# 03-2G.net
KiCad netlist of a schematic drawn in Altium Designer
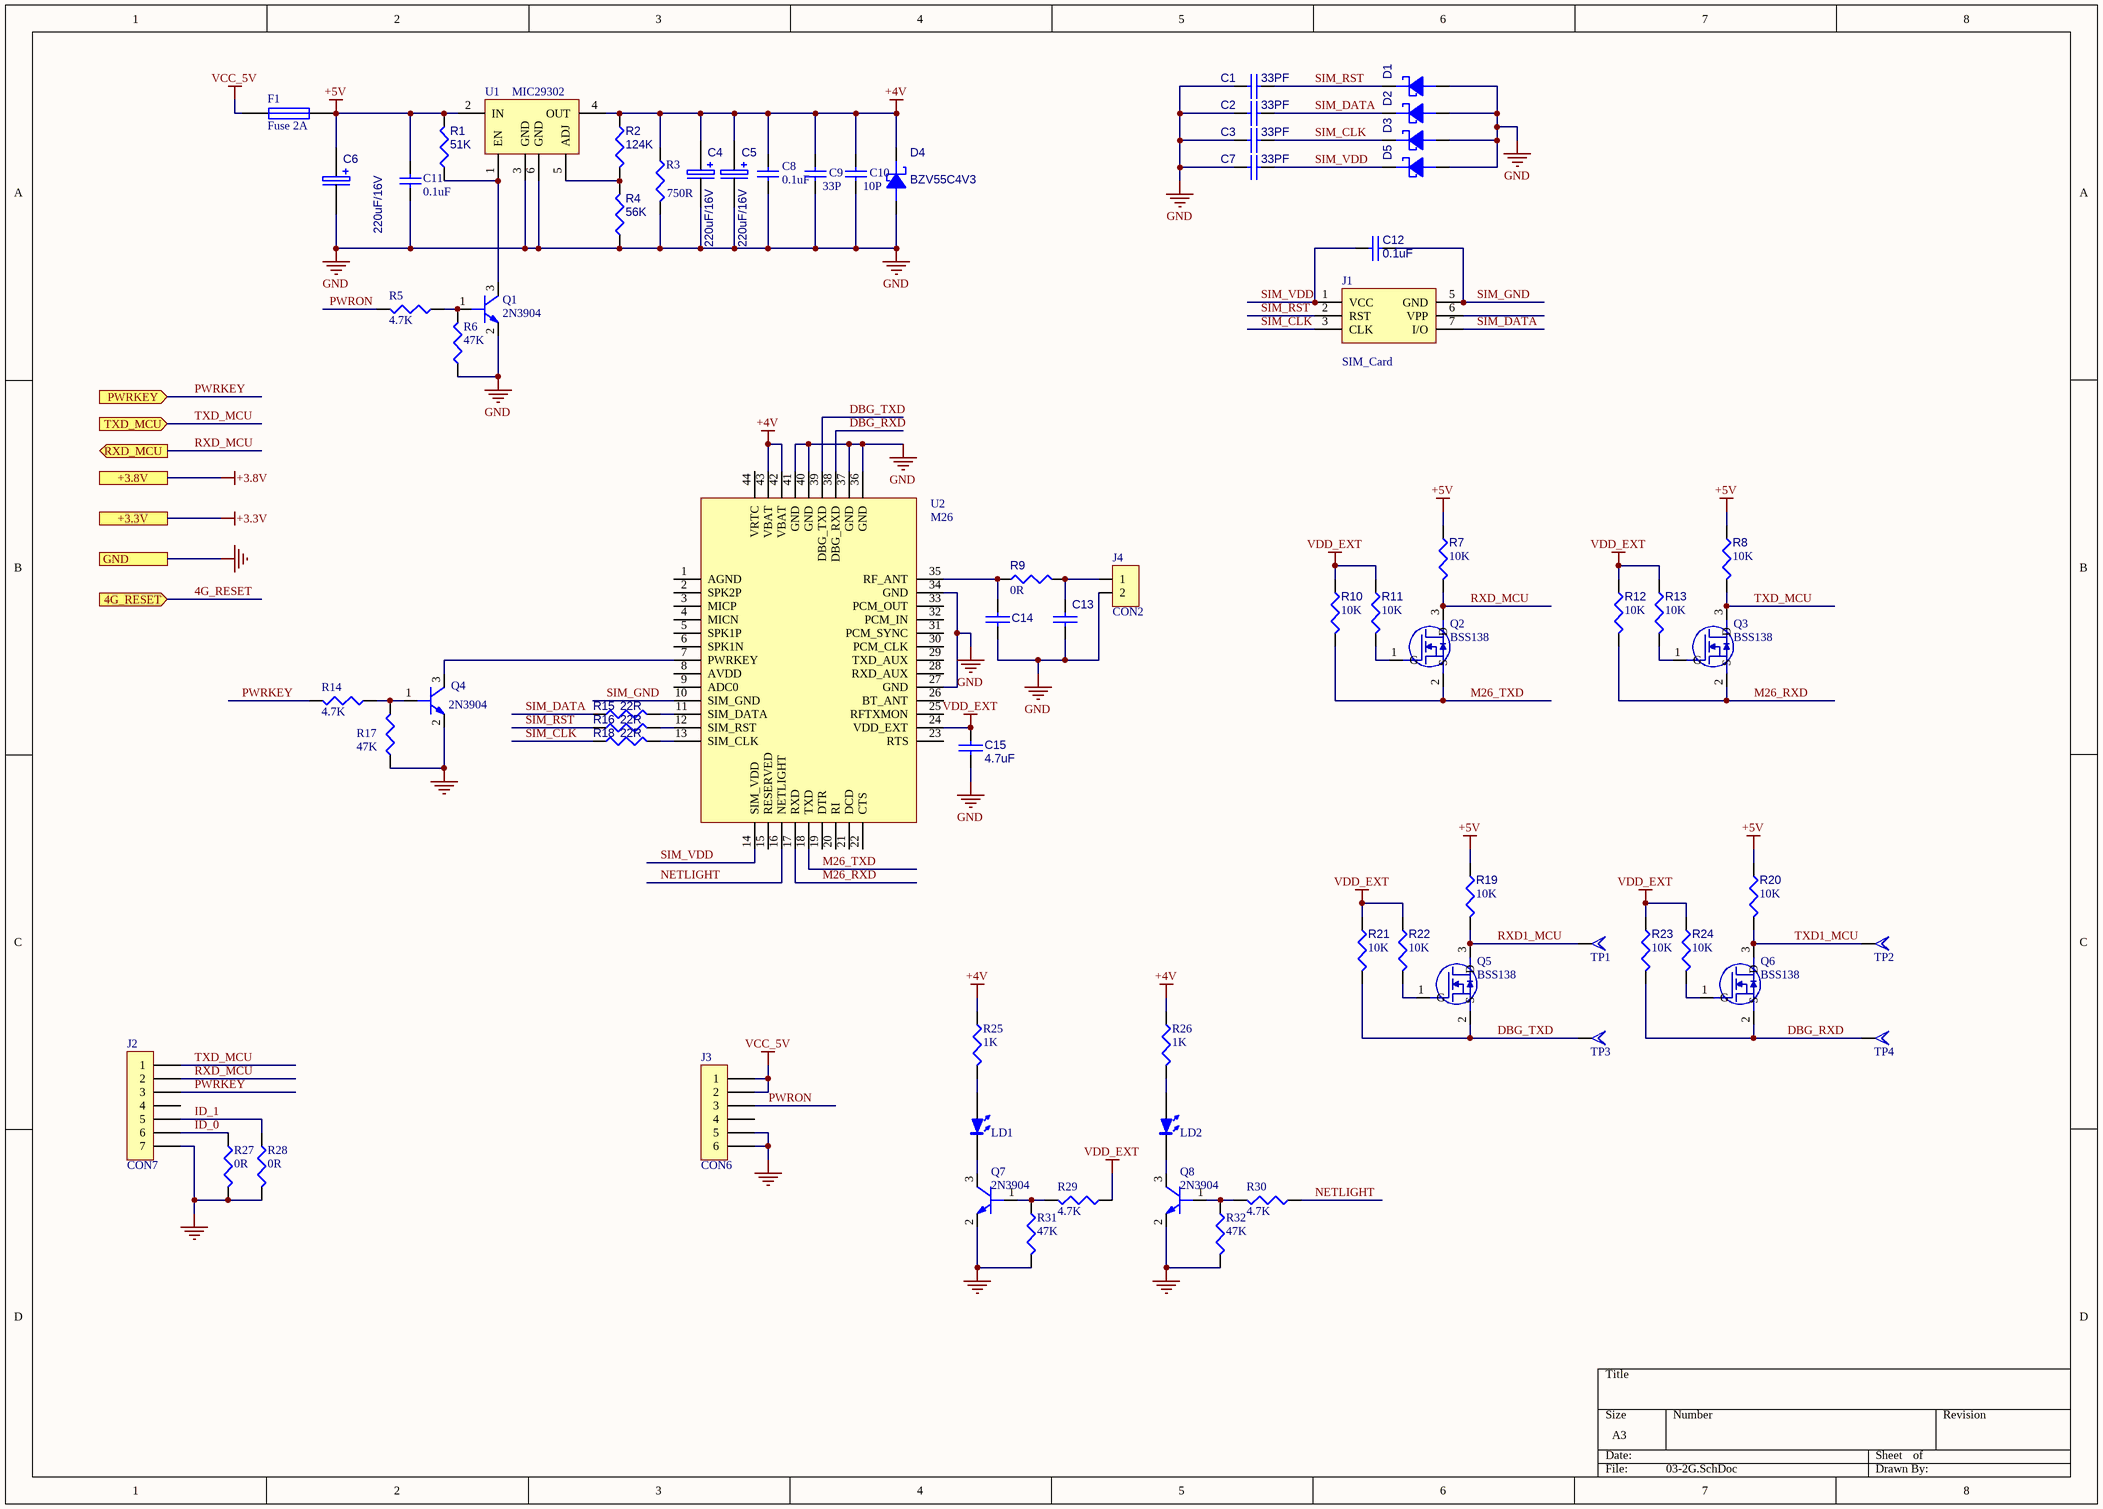
[diagram p0: 03-2G.SchDoc]

(export (version "E")
  (design (tool "Eeschema 10.0.6"))
  (components
    (comp (ref "C1")
      (value "33PF")
      (footprint "0603_C")
      (description "CAP")
      (libsource (lib "*") (part "CAP"))
    )
    (comp (ref "C2")
      (value "33PF")
      (footprint "0603_C")
      (description "CAP")
      (libsource (lib "*") (part "CAP"))
    )
    (comp (ref "C3")
      (value "33PF")
      (footprint "0603_C")
      (description "CAP")
      (libsource (lib "*") (part "CAP"))
    )
    (comp (ref "C4")
      (value "220uF/16V")
      (footprint "C_TAN_D")
      (description "E-CAP")
      (libsource (lib "*") (part "ECAP"))
    )
    (comp (ref "C5")
      (value "220uF/16V")
      (footprint "C_TAN_D")
      (description "E-CAP")
      (libsource (lib "*") (part "ECAP"))
    )
    (comp (ref "C6")
      (value "220uF/16V")
      (footprint "C_TAN_D")
      (description "E-CAP")
      (libsource (lib "*") (part "ECAP"))
    )
    (comp (ref "C7")
      (value "33PF")
      (footprint "0603_C")
      (description "CAP")
      (libsource (lib "*") (part "CAP"))
    )
    (comp (ref "C8")
      (value "0.1uF")
      (footprint "0603_C")
      (description "Capacitor")
      (fields (field (name "PUBLISHER") "Altium Limited"))
      (libsource (lib "EP_MCB_V3.00") (part "Cap Semi"))
    )
    (comp (ref "C9")
      (value "33P")
      (footprint "0603_C")
      (description "Capacitor")
      (fields (field (name "PUBLISHER") "Altium Limited"))
      (libsource (lib "EP_MCB_V3.00") (part "Cap Semi"))
    )
    (comp (ref "C10")
      (value "10P")
      (footprint "0603_C")
      (description "Capacitor")
      (fields (field (name "PUBLISHER") "Altium Limited"))
      (libsource (lib "EP_MCB_V3.00") (part "Cap Semi"))
    )
    (comp (ref "C11")
      (value "0.1uF")
      (footprint "0603_C")
      (description "Capacitor")
      (fields (field (name "PUBLISHER") "Altium Limited"))
      (libsource (lib "EP_MCB_V3.00") (part "Cap Semi"))
    )
    (comp (ref "C12")
      (value "0.1uF")
      (footprint "0603_C")
      (description "CAP")
      (libsource (lib "*") (part "CAP"))
    )
    (comp (ref "C13")
      (value "NC")
      (footprint "0603_r")
      (description "CAP")
      (libsource (lib "") (part "CAP_1"))
    )
    (comp (ref "C14")
      (value "NC")
      (footprint "0603_r")
      (description "CAP")
      (libsource (lib "") (part "CAP_1"))
    )
    (comp (ref "C15")
      (value "4.7uF")
      (footprint "0603_C")
      (description "CAP")
      (libsource (lib "") (part "CAP_1"))
    )
    (comp (ref "D1")
      (value "ESD9M5.0ST5G")
      (footprint "SOD-923")
      (libsource (lib "EP_MCB_V4.1") (part "DIODE SCHOTTKY"))
    )
    (comp (ref "D2")
      (value "ESD9M5.0ST5G")
      (footprint "SOD-923")
      (libsource (lib "EP_MCB_V4.1") (part "DIODE SCHOTTKY"))
    )
    (comp (ref "D3")
      (value "ESD9M5.0ST5G")
      (footprint "SOD-923")
      (libsource (lib "EP_MCB_V4.1") (part "DIODE SCHOTTKY"))
    )
    (comp (ref "D4")
      (value "BZV55C4V3")
      (footprint "SOD-80")
      (libsource (lib "EP_MCB_V4.1") (part "DIODE SCHOTTKY"))
    )
    (comp (ref "D5")
      (value "ESD9M5.0ST5G")
      (footprint "SOD-923")
      (libsource (lib "EP_MCB_V4.1") (part "DIODE SCHOTTKY"))
    )
    (comp (ref "F1")
      (value "Fuse 2A")
      (footprint "1812_F")
      (description "Fuse")
      (fields (field (name "PUBLISHER") "Altium Limited"))
      (libsource (lib "Miscellaneous Devices") (part "Fuse 1"))
    )
    (comp (ref "J1")
      (value "SIM_Card")
      (footprint "MicroSIM-6")
      (libsource (lib "MySchlib") (part "SIM_Card"))
    )
    (comp (ref "J2") (value "CON7") (footprint "SIP7") (libsource (lib "MySchlib") (part "CON7")))
    (comp (ref "J3") (value "CON6") (footprint "SIP6") (libsource (lib "MySchlib") (part "CON6")))
    (comp (ref "J4") (value "CON2") (footprint "RF-Z") (libsource (lib "MySchlib") (part "CON2")))
    (comp (ref "LD1")
      (value "WHITE")
      (footprint "LED_0603")
      (description "LED")
      (libsource (lib "*") (part "LED"))
    )
    (comp (ref "LD2")
      (value "WHITE")
      (footprint "LED_0603")
      (description "LED")
      (libsource (lib "*") (part "LED"))
    )
    (comp (ref "Q1") (value "2N3904") (footprint "SOT23") (libsource (lib "MySchlib") (part "NPN")))
    (comp (ref "Q2")
      (value "BSS138")
      (footprint "SOT23")
      (description "N-Channel Enhancement MOSFET")
      (libsource (lib "EP_MCB_V6.0") (part "N-Channel Enhancement MOSFET"))
    )
    (comp (ref "Q3")
      (value "BSS138")
      (footprint "SOT23")
      (description "N-Channel Enhancement MOSFET")
      (libsource (lib "EP_MCB_V6.0") (part "N-Channel Enhancement MOSFET"))
    )
    (comp (ref "Q4") (value "2N3904") (footprint "SOT23") (libsource (lib "MySchlib") (part "NPN")))
    (comp (ref "Q5")
      (value "BSS138")
      (footprint "SOT23")
      (description "N-Channel Enhancement MOSFET")
      (libsource (lib "EP_MCB_V6.0") (part "N-Channel Enhancement MOSFET"))
    )
    (comp (ref "Q6")
      (value "BSS138")
      (footprint "SOT23")
      (description "N-Channel Enhancement MOSFET")
      (libsource (lib "EP_MCB_V6.0") (part "N-Channel Enhancement MOSFET"))
    )
    (comp (ref "Q7") (value "2N3904") (footprint "SOT23") (libsource (lib "MySchlib") (part "NPN")))
    (comp (ref "Q8") (value "2N3904") (footprint "SOT23") (libsource (lib "MySchlib") (part "NPN")))
    (comp (ref "R1")
      (value "51K")
      (footprint "0603_R")
      (description "RESISTOR")
      (libsource (lib "*") (part "R0.25W"))
    )
    (comp (ref "R2")
      (value "124K")
      (footprint "0603_R")
      (description "RESISTOR")
      (libsource (lib "*") (part "R0.25W"))
    )
    (comp (ref "R3") (value "750R") (footprint "0603_R") (libsource (lib "") (part "RES1_1")))
    (comp (ref "R4")
      (value "56K")
      (footprint "0603_R")
      (description "RESISTOR")
      (libsource (lib "*") (part "R0.25W"))
    )
    (comp (ref "R5") (value "4.7K") (footprint "0603_R") (libsource (lib "MySchlib") (part "RES1")))
    (comp (ref "R6") (value "47K") (footprint "0603_R") (libsource (lib "MySchlib") (part "RES1")))
    (comp (ref "R7")
      (value "10K")
      (footprint "0603_R")
      (description "Resistor")
      (fields (field (name "PUBLISHER") "Altium Limited"))
      (libsource (lib "EP_MCB_V6.0") (part "Res3_3"))
    )
    (comp (ref "R8")
      (value "10K")
      (footprint "0603_R")
      (description "Resistor")
      (fields (field (name "PUBLISHER") "Altium Limited"))
      (libsource (lib "EP_MCB_V6.0") (part "Res3_3"))
    )
    (comp (ref "R9")
      (value "0R")
      (footprint "0603_R")
      (description "Resistor")
      (fields (field (name "PUBLISHER") "Altium Limited"))
      (libsource (lib "EP_MCB_V6.0") (part "Res3_3"))
    )
    (comp (ref "R10")
      (value "10K")
      (footprint "0603_R")
      (description "Resistor")
      (fields (field (name "PUBLISHER") "Altium Limited"))
      (libsource (lib "EP_MCB_V6.0") (part "Res3_3"))
    )
    (comp (ref "R11")
      (value "10K")
      (footprint "0603_R")
      (description "Resistor")
      (fields (field (name "PUBLISHER") "Altium Limited"))
      (libsource (lib "EP_MCB_V6.0") (part "Res3_3"))
    )
    (comp (ref "R12")
      (value "10K")
      (footprint "0603_R")
      (description "Resistor")
      (fields (field (name "PUBLISHER") "Altium Limited"))
      (libsource (lib "EP_MCB_V6.0") (part "Res3_3"))
    )
    (comp (ref "R13")
      (value "10K")
      (footprint "0603_R")
      (description "Resistor")
      (fields (field (name "PUBLISHER") "Altium Limited"))
      (libsource (lib "EP_MCB_V6.0") (part "Res3_3"))
    )
    (comp (ref "R14") (value "4.7K") (footprint "0603_R") (libsource (lib "MySchlib") (part "RES1")))
    (comp (ref "R15")
      (value "22R")
      (footprint "0603_R")
      (description "RESISTOR")
      (libsource (lib "*") (part "R0.25W"))
    )
    (comp (ref "R16")
      (value "22R")
      (footprint "0603_R")
      (description "RESISTOR")
      (libsource (lib "*") (part "R0.25W"))
    )
    (comp (ref "R17") (value "47K") (footprint "0603_R") (libsource (lib "MySchlib") (part "RES1")))
    (comp (ref "R18")
      (value "22R")
      (footprint "0603_R")
      (description "RESISTOR")
      (libsource (lib "*") (part "R0.25W"))
    )
    (comp (ref "R19")
      (value "10K")
      (footprint "0603_R")
      (description "Resistor")
      (fields (field (name "PUBLISHER") "Altium Limited"))
      (libsource (lib "EP_MCB_V6.0") (part "Res3_3"))
    )
    (comp (ref "R20")
      (value "10K")
      (footprint "0603_R")
      (description "Resistor")
      (fields (field (name "PUBLISHER") "Altium Limited"))
      (libsource (lib "EP_MCB_V6.0") (part "Res3_3"))
    )
    (comp (ref "R21")
      (value "10K")
      (footprint "0603_R")
      (description "Resistor")
      (fields (field (name "PUBLISHER") "Altium Limited"))
      (libsource (lib "EP_MCB_V6.0") (part "Res3_3"))
    )
    (comp (ref "R22")
      (value "10K")
      (footprint "0603_R")
      (description "Resistor")
      (fields (field (name "PUBLISHER") "Altium Limited"))
      (libsource (lib "EP_MCB_V6.0") (part "Res3_3"))
    )
    (comp (ref "R23")
      (value "10K")
      (footprint "0603_R")
      (description "Resistor")
      (fields (field (name "PUBLISHER") "Altium Limited"))
      (libsource (lib "EP_MCB_V6.0") (part "Res3_3"))
    )
    (comp (ref "R24")
      (value "10K")
      (footprint "0603_R")
      (description "Resistor")
      (fields (field (name "PUBLISHER") "Altium Limited"))
      (libsource (lib "EP_MCB_V6.0") (part "Res3_3"))
    )
    (comp (ref "R25") (value "1K") (footprint "0603_R") (libsource (lib "MySchlib") (part "RES1")))
    (comp (ref "R26") (value "1K") (footprint "0603_R") (libsource (lib "MySchlib") (part "RES1")))
    (comp (ref "R27") (value "0R") (footprint "0603_R") (libsource (lib "MySchlib") (part "RES1")))
    (comp (ref "R28") (value "0R") (footprint "0603_R") (libsource (lib "MySchlib") (part "RES1")))
    (comp (ref "R29") (value "4.7K") (footprint "0603_R") (libsource (lib "MySchlib") (part "RES1")))
    (comp (ref "R30") (value "4.7K") (footprint "0603_R") (libsource (lib "MySchlib") (part "RES1")))
    (comp (ref "R31") (value "47K") (footprint "0603_R") (libsource (lib "MySchlib") (part "RES1")))
    (comp (ref "R32") (value "47K") (footprint "0603_R") (libsource (lib "MySchlib") (part "RES1")))
    (comp (ref "TP1")
      (value "Component_1")
      (footprint "TP-40")
      (libsource (lib "MySchlib") (part "Component_1"))
    )
    (comp (ref "TP2")
      (value "Component_1")
      (footprint "TP-40")
      (libsource (lib "MySchlib") (part "Component_1"))
    )
    (comp (ref "TP3")
      (value "Component_1")
      (footprint "TP-40")
      (libsource (lib "MySchlib") (part "Component_1"))
    )
    (comp (ref "TP4")
      (value "Component_1")
      (footprint "TP-40")
      (libsource (lib "MySchlib") (part "Component_1"))
    )
    (comp (ref "U1") (value "MIC29302") (footprint "TO-263-5") (libsource (lib "MySchlib") (part "MIC29302")))
    (comp (ref "U2") (value "M26") (footprint "M26") (libsource (lib "MySchlib") (part "M26")))
  )
  (nets
    (net (code "3") (name "+4V") (class "Default")
      (node (ref "C10") (pin "2") (pinfunction "2_2") (pintype "passive"))
      (node (ref "C4") (pin "1") (pinfunction "+_1") (pintype "passive"))
      (node (ref "C5") (pin "1") (pinfunction "+_1") (pintype "passive"))
      (node (ref "C8") (pin "2") (pinfunction "2_2") (pintype "passive"))
      (node (ref "C9") (pin "2") (pinfunction "2_2") (pintype "passive"))
      (node (ref "D4") (pin "2") (pinfunction "CATHODE_2") (pintype "passive"))
      (node (ref "R2") (pin "2") (pinfunction "2_2") (pintype "passive"))
      (node (ref "R25") (pin "1") (pinfunction "1_1") (pintype "passive"))
      (node (ref "R26") (pin "1") (pinfunction "1_1") (pintype "passive"))
      (node (ref "R3") (pin "2") (pinfunction "2_2") (pintype "passive"))
      (node (ref "U1") (pin "4") (pinfunction "OUT_4") (pintype "passive"))
      (node (ref "U2") (pin "42") (pinfunction "VBAT_42") (pintype "passive"))
      (node (ref "U2") (pin "43") (pinfunction "VBAT_43") (pintype "passive"))
    )
    (net (code "4") (name "+5V") (class "Default")
      (node (ref "C11") (pin "2") (pinfunction "2_2") (pintype "passive"))
      (node (ref "C6") (pin "1") (pinfunction "+_1") (pintype "passive"))
      (node (ref "F1") (pin "2") (pinfunction "2_2") (pintype "passive"))
      (node (ref "R1") (pin "1") (pinfunction "1_1") (pintype "passive"))
      (node (ref "R19") (pin "1") (pinfunction "1_1") (pintype "passive"))
      (node (ref "R20") (pin "1") (pinfunction "1_1") (pintype "passive"))
      (node (ref "R7") (pin "1") (pinfunction "1_1") (pintype "passive"))
      (node (ref "R8") (pin "1") (pinfunction "1_1") (pintype "passive"))
      (node (ref "U1") (pin "2") (pinfunction "IN_2") (pintype "passive"))
    )
    (net (code "6") (name "/DBG_RXD") (class "Default")
      (node (ref "Q6") (pin "2") (pinfunction "S_2") (pintype "passive"))
      (node (ref "R23") (pin "2") (pinfunction "2_2") (pintype "passive"))
      (node (ref "TP4") (pin "1") (pinfunction "1_1") (pintype "passive"))
      (node (ref "U2") (pin "38") (pinfunction "DBG_RXD_38") (pintype "passive"))
    )
    (net (code "7") (name "/DBG_TXD") (class "Default")
      (node (ref "Q5") (pin "2") (pinfunction "S_2") (pintype "passive"))
      (node (ref "R21") (pin "2") (pinfunction "2_2") (pintype "passive"))
      (node (ref "TP3") (pin "1") (pinfunction "1_1") (pintype "passive"))
      (node (ref "U2") (pin "39") (pinfunction "DBG_TXD_39") (pintype "passive"))
    )
    (net (code "8") (name "/ID_0") (class "Default")
      (node (ref "J2") (pin "6") (pinfunction "6_6") (pintype "passive"))
      (node (ref "R27") (pin "1") (pinfunction "1_1") (pintype "passive"))
    )
    (net (code "9") (name "/ID_1") (class "Default")
      (node (ref "J2") (pin "5") (pinfunction "5_5") (pintype "passive"))
      (node (ref "R28") (pin "1") (pinfunction "1_1") (pintype "passive"))
    )
    (net (code "10") (name "/M26_RXD") (class "Default")
      (node (ref "Q3") (pin "2") (pinfunction "S_2") (pintype "passive"))
      (node (ref "R12") (pin "2") (pinfunction "2_2") (pintype "passive"))
      (node (ref "U2") (pin "17") (pinfunction "RXD_17") (pintype "passive"))
    )
    (net (code "11") (name "/M26_TXD") (class "Default")
      (node (ref "Q2") (pin "2") (pinfunction "S_2") (pintype "passive"))
      (node (ref "R10") (pin "2") (pinfunction "2_2") (pintype "passive"))
      (node (ref "U2") (pin "18") (pinfunction "TXD_18") (pintype "passive"))
    )
    (net (code "12") (name "/NETLIGHT") (class "Default")
      (node (ref "R30") (pin "1") (pinfunction "1_1") (pintype "passive"))
      (node (ref "U2") (pin "16") (pinfunction "NETLIGHT_16") (pintype "passive"))
    )
    (net (code "13") (name "/PWRKEY") (class "Default")
      (node (ref "J2") (pin "3") (pinfunction "3_3") (pintype "passive"))
      (node (ref "R14") (pin "1") (pinfunction "1_1") (pintype "passive"))
    )
    (net (code "14") (name "/PWRON") (class "Default")
      (node (ref "J3") (pin "3") (pinfunction "3_3") (pintype "passive"))
      (node (ref "R5") (pin "1") (pinfunction "1_1") (pintype "passive"))
    )
    (net (code "15") (name "/RXD1_MCU") (class "Default")
      (node (ref "Q5") (pin "3") (pinfunction "D_3") (pintype "passive"))
      (node (ref "R19") (pin "2") (pinfunction "2_2") (pintype "passive"))
      (node (ref "TP1") (pin "1") (pinfunction "1_1") (pintype "passive"))
    )
    (net (code "16") (name "/RXD_MCU") (class "Default")
      (node (ref "J2") (pin "2") (pinfunction "2_2") (pintype "passive"))
      (node (ref "Q2") (pin "3") (pinfunction "D_3") (pintype "passive"))
      (node (ref "R7") (pin "2") (pinfunction "2_2") (pintype "passive"))
    )
    (net (code "17") (name "/SIM_CLK") (class "Default")
      (node (ref "C3") (pin "2") (pinfunction "2_2") (pintype "passive"))
      (node (ref "D3") (pin "2") (pinfunction "CATHODE_2") (pintype "passive"))
      (node (ref "J1") (pin "3") (pinfunction "CLK_3") (pintype "passive"))
      (node (ref "R18") (pin "1") (pinfunction "1_1") (pintype "passive"))
    )
    (net (code "18") (name "/SIM_DATA") (class "Default")
      (node (ref "C2") (pin "2") (pinfunction "2_2") (pintype "passive"))
      (node (ref "D2") (pin "2") (pinfunction "CATHODE_2") (pintype "passive"))
      (node (ref "J1") (pin "7") (pinfunction "I/O_7") (pintype "passive"))
      (node (ref "R15") (pin "1") (pinfunction "1_1") (pintype "passive"))
    )
    (net (code "19") (name "/SIM_GND") (class "Default")
      (node (ref "C12") (pin "2") (pinfunction "2_2") (pintype "passive"))
      (node (ref "J1") (pin "5") (pinfunction "GND_5") (pintype "passive"))
      (node (ref "U2") (pin "10") (pinfunction "SIM_GND_10") (pintype "passive"))
    )
    (net (code "20") (name "/SIM_RST") (class "Default")
      (node (ref "C1") (pin "2") (pinfunction "2_2") (pintype "passive"))
      (node (ref "D1") (pin "2") (pinfunction "CATHODE_2") (pintype "passive"))
      (node (ref "J1") (pin "2") (pinfunction "RST_2") (pintype "passive"))
      (node (ref "R16") (pin "1") (pinfunction "1_1") (pintype "passive"))
    )
    (net (code "21") (name "/SIM_VDD") (class "Default")
      (node (ref "C12") (pin "1") (pinfunction "1_1") (pintype "passive"))
      (node (ref "C7") (pin "2") (pinfunction "2_2") (pintype "passive"))
      (node (ref "D5") (pin "2") (pinfunction "CATHODE_2") (pintype "passive"))
      (node (ref "J1") (pin "1") (pinfunction "VCC_1") (pintype "passive"))
      (node (ref "U2") (pin "14") (pinfunction "SIM_VDD_14") (pintype "passive"))
    )
    (net (code "22") (name "/TXD1_MCU") (class "Default")
      (node (ref "Q6") (pin "3") (pinfunction "D_3") (pintype "passive"))
      (node (ref "R20") (pin "2") (pinfunction "2_2") (pintype "passive"))
      (node (ref "TP2") (pin "1") (pinfunction "1_1") (pintype "passive"))
    )
    (net (code "23") (name "/TXD_MCU") (class "Default")
      (node (ref "J2") (pin "1") (pinfunction "1_1") (pintype "passive"))
      (node (ref "Q3") (pin "3") (pinfunction "D_3") (pintype "passive"))
      (node (ref "R8") (pin "2") (pinfunction "2_2") (pintype "passive"))
    )
    (net (code "24") (name "GND") (class "Default")
      (node (ref "C1") (pin "1") (pinfunction "1_1") (pintype "passive"))
      (node (ref "C10") (pin "1") (pinfunction "1_1") (pintype "passive"))
      (node (ref "C11") (pin "1") (pinfunction "1_1") (pintype "passive"))
      (node (ref "C13") (pin "2") (pinfunction "2_2") (pintype "passive"))
      (node (ref "C14") (pin "2") (pinfunction "2_2") (pintype "passive"))
      (node (ref "C15") (pin "2") (pinfunction "2_2") (pintype "passive"))
      (node (ref "C2") (pin "1") (pinfunction "1_1") (pintype "passive"))
      (node (ref "C3") (pin "1") (pinfunction "1_1") (pintype "passive"))
      (node (ref "C4") (pin "2") (pinfunction "-_2") (pintype "passive"))
      (node (ref "C5") (pin "2") (pinfunction "-_2") (pintype "passive"))
      (node (ref "C6") (pin "2") (pinfunction "-_2") (pintype "passive"))
      (node (ref "C7") (pin "1") (pinfunction "1_1") (pintype "passive"))
      (node (ref "C8") (pin "1") (pinfunction "1_1") (pintype "passive"))
      (node (ref "C9") (pin "1") (pinfunction "1_1") (pintype "passive"))
      (node (ref "D1") (pin "1") (pinfunction "ANODE_1") (pintype "passive"))
      (node (ref "D2") (pin "1") (pinfunction "ANODE_1") (pintype "passive"))
      (node (ref "D3") (pin "1") (pinfunction "ANODE_1") (pintype "passive"))
      (node (ref "D4") (pin "1") (pinfunction "ANODE_1") (pintype "passive"))
      (node (ref "D5") (pin "1") (pinfunction "ANODE_1") (pintype "passive"))
      (node (ref "J2") (pin "7") (pinfunction "7_7") (pintype "passive"))
      (node (ref "J3") (pin "5") (pinfunction "5_5") (pintype "passive"))
      (node (ref "J3") (pin "6") (pinfunction "6_6") (pintype "passive"))
      (node (ref "J4") (pin "2") (pinfunction "2_2") (pintype "passive"))
      (node (ref "Q1") (pin "2") (pinfunction "EMITTER_2") (pintype "passive"))
      (node (ref "Q4") (pin "2") (pinfunction "EMITTER_2") (pintype "passive"))
      (node (ref "Q7") (pin "2") (pinfunction "EMITTER_2") (pintype "passive"))
      (node (ref "Q8") (pin "2") (pinfunction "EMITTER_2") (pintype "passive"))
      (node (ref "R17") (pin "2") (pinfunction "2_2") (pintype "passive"))
      (node (ref "R27") (pin "2") (pinfunction "2_2") (pintype "passive"))
      (node (ref "R28") (pin "2") (pinfunction "2_2") (pintype "passive"))
      (node (ref "R3") (pin "1") (pinfunction "1_1") (pintype "passive"))
      (node (ref "R31") (pin "2") (pinfunction "2_2") (pintype "passive"))
      (node (ref "R32") (pin "2") (pinfunction "2_2") (pintype "passive"))
      (node (ref "R4") (pin "2") (pinfunction "2_2") (pintype "passive"))
      (node (ref "R6") (pin "2") (pinfunction "2_2") (pintype "passive"))
      (node (ref "U1") (pin "3") (pinfunction "GND_3") (pintype "passive"))
      (node (ref "U1") (pin "6") (pinfunction "GND_6") (pintype "passive"))
      (node (ref "U2") (pin "27") (pinfunction "GND_27") (pintype "passive"))
      (node (ref "U2") (pin "34") (pinfunction "GND_34") (pintype "passive"))
      (node (ref "U2") (pin "36") (pinfunction "GND_36") (pintype "passive"))
      (node (ref "U2") (pin "37") (pinfunction "GND_37") (pintype "passive"))
      (node (ref "U2") (pin "40") (pinfunction "GND_40") (pintype "passive"))
      (node (ref "U2") (pin "41") (pinfunction "GND_41") (pintype "passive"))
    )
    (net (code "25") (name "Net-(C13-Pad1)") (class "Default")
      (node (ref "C13") (pin "1") (pinfunction "1_1") (pintype "passive"))
      (node (ref "J4") (pin "1") (pinfunction "1_1") (pintype "passive"))
      (node (ref "R9") (pin "2") (pinfunction "2_2") (pintype "passive"))
    )
    (net (code "26") (name "Net-(LD1-PadA)") (class "Default")
      (node (ref "LD1") (pin "A") (pinfunction "A_A") (pintype "passive"))
      (node (ref "R25") (pin "2") (pinfunction "2_2") (pintype "passive"))
    )
    (net (code "27") (name "Net-(LD2-PadA)") (class "Default")
      (node (ref "LD2") (pin "A") (pinfunction "A_A") (pintype "passive"))
      (node (ref "R26") (pin "2") (pinfunction "2_2") (pintype "passive"))
    )
    (net (code "28") (name "Net-(Q1-BASE)") (class "Default")
      (node (ref "Q1") (pin "1") (pinfunction "BASE_1") (pintype "passive"))
      (node (ref "R5") (pin "2") (pinfunction "2_2") (pintype "passive"))
      (node (ref "R6") (pin "1") (pinfunction "1_1") (pintype "passive"))
    )
    (net (code "29") (name "Net-(Q1-COLLECTOR)") (class "Default")
      (node (ref "Q1") (pin "3") (pinfunction "COLLECTOR_3") (pintype "passive"))
      (node (ref "R1") (pin "2") (pinfunction "2_2") (pintype "passive"))
      (node (ref "U1") (pin "1") (pinfunction "EN_1") (pintype "passive"))
    )
    (net (code "30") (name "Net-(Q2-G)") (class "Default")
      (node (ref "Q2") (pin "1") (pinfunction "G_1") (pintype "passive"))
      (node (ref "R11") (pin "2") (pinfunction "2_2") (pintype "passive"))
    )
    (net (code "31") (name "Net-(Q3-G)") (class "Default")
      (node (ref "Q3") (pin "1") (pinfunction "G_1") (pintype "passive"))
      (node (ref "R13") (pin "2") (pinfunction "2_2") (pintype "passive"))
    )
    (net (code "32") (name "Net-(Q4-BASE)") (class "Default")
      (node (ref "Q4") (pin "1") (pinfunction "BASE_1") (pintype "passive"))
      (node (ref "R14") (pin "2") (pinfunction "2_2") (pintype "passive"))
      (node (ref "R17") (pin "1") (pinfunction "1_1") (pintype "passive"))
    )
    (net (code "33") (name "Net-(Q4-COLLECTOR)") (class "Default")
      (node (ref "Q4") (pin "3") (pinfunction "COLLECTOR_3") (pintype "passive"))
      (node (ref "U2") (pin "7") (pinfunction "PWRKEY_7") (pintype "passive"))
    )
    (net (code "34") (name "Net-(Q5-G)") (class "Default")
      (node (ref "Q5") (pin "1") (pinfunction "G_1") (pintype "passive"))
      (node (ref "R22") (pin "2") (pinfunction "2_2") (pintype "passive"))
    )
    (net (code "35") (name "Net-(Q6-G)") (class "Default")
      (node (ref "Q6") (pin "1") (pinfunction "G_1") (pintype "passive"))
      (node (ref "R24") (pin "2") (pinfunction "2_2") (pintype "passive"))
    )
    (net (code "36") (name "Net-(Q7-BASE)") (class "Default")
      (node (ref "Q7") (pin "1") (pinfunction "BASE_1") (pintype "passive"))
      (node (ref "R29") (pin "2") (pinfunction "2_2") (pintype "passive"))
      (node (ref "R31") (pin "1") (pinfunction "1_1") (pintype "passive"))
    )
    (net (code "37") (name "Net-(Q7-COLLECTOR)") (class "Default")
      (node (ref "LD1") (pin "K") (pinfunction "K_K") (pintype "passive"))
      (node (ref "Q7") (pin "3") (pinfunction "COLLECTOR_3") (pintype "passive"))
    )
    (net (code "38") (name "Net-(Q8-BASE)") (class "Default")
      (node (ref "Q8") (pin "1") (pinfunction "BASE_1") (pintype "passive"))
      (node (ref "R30") (pin "2") (pinfunction "2_2") (pintype "passive"))
      (node (ref "R32") (pin "1") (pinfunction "1_1") (pintype "passive"))
    )
    (net (code "39") (name "Net-(Q8-COLLECTOR)") (class "Default")
      (node (ref "LD2") (pin "K") (pinfunction "K_K") (pintype "passive"))
      (node (ref "Q8") (pin "3") (pinfunction "COLLECTOR_3") (pintype "passive"))
    )
    (net (code "40") (name "Net-(U1-ADJ)") (class "Default")
      (node (ref "R2") (pin "1") (pinfunction "1_1") (pintype "passive"))
      (node (ref "R4") (pin "1") (pinfunction "1_1") (pintype "passive"))
      (node (ref "U1") (pin "5") (pinfunction "ADJ_5") (pintype "passive"))
    )
    (net (code "41") (name "Net-(U2-RF_ANT)") (class "Default")
      (node (ref "C14") (pin "1") (pinfunction "1_1") (pintype "passive"))
      (node (ref "R9") (pin "1") (pinfunction "1_1") (pintype "passive"))
      (node (ref "U2") (pin "35") (pinfunction "RF_ANT_35") (pintype "passive"))
    )
    (net (code "42") (name "Net-(U2-SIM_CLK)") (class "Default")
      (node (ref "R18") (pin "2") (pinfunction "2_2") (pintype "passive"))
      (node (ref "U2") (pin "13") (pinfunction "SIM_CLK_13") (pintype "passive"))
    )
    (net (code "43") (name "Net-(U2-SIM_DATA)") (class "Default")
      (node (ref "R15") (pin "2") (pinfunction "2_2") (pintype "passive"))
      (node (ref "U2") (pin "11") (pinfunction "SIM_DATA_11") (pintype "passive"))
    )
    (net (code "44") (name "Net-(U2-SIM_RST)") (class "Default")
      (node (ref "R16") (pin "2") (pinfunction "2_2") (pintype "passive"))
      (node (ref "U2") (pin "12") (pinfunction "SIM_RST_12") (pintype "passive"))
    )
    (net (code "45") (name "VCC_5V") (class "Default")
      (node (ref "F1") (pin "1") (pinfunction "1_1") (pintype "passive"))
      (node (ref "J3") (pin "1") (pinfunction "1_1") (pintype "passive"))
      (node (ref "J3") (pin "2") (pinfunction "2_2") (pintype "passive"))
    )
    (net (code "46") (name "VDD_EXT") (class "Default")
      (node (ref "C15") (pin "1") (pinfunction "1_1") (pintype "passive"))
      (node (ref "R10") (pin "1") (pinfunction "1_1") (pintype "passive"))
      (node (ref "R11") (pin "1") (pinfunction "1_1") (pintype "passive"))
      (node (ref "R12") (pin "1") (pinfunction "1_1") (pintype "passive"))
      (node (ref "R13") (pin "1") (pinfunction "1_1") (pintype "passive"))
      (node (ref "R21") (pin "1") (pinfunction "1_1") (pintype "passive"))
      (node (ref "R22") (pin "1") (pinfunction "1_1") (pintype "passive"))
      (node (ref "R23") (pin "1") (pinfunction "1_1") (pintype "passive"))
      (node (ref "R24") (pin "1") (pinfunction "1_1") (pintype "passive"))
      (node (ref "R29") (pin "1") (pinfunction "1_1") (pintype "passive"))
      (node (ref "U2") (pin "24") (pinfunction "VDD_EXT_24") (pintype "passive"))
    )
    (net (code "47") (name "unconnected-(J1-VPP-Pad6)") (class "Default")
      (node (ref "J1") (pin "6") (pinfunction "VPP_6") (pintype "passive"))
    )
    (net (code "48") (name "unconnected-(J2-Pad4)") (class "Default")
      (node (ref "J2") (pin "4") (pinfunction "4_4") (pintype "passive"))
    )
    (net (code "49") (name "unconnected-(J3-Pad4)") (class "Default")
      (node (ref "J3") (pin "4") (pinfunction "4_4") (pintype "passive"))
    )
    (net (code "50") (name "unconnected-(U2-ADC0-Pad9)") (class "Default")
      (node (ref "U2") (pin "9") (pinfunction "ADC0_9") (pintype "passive"))
    )
    (net (code "51") (name "unconnected-(U2-AGND-Pad1)") (class "Default")
      (node (ref "U2") (pin "1") (pinfunction "AGND_1") (pintype "passive"))
    )
    (net (code "52") (name "unconnected-(U2-AVDD-Pad8)") (class "Default")
      (node (ref "U2") (pin "8") (pinfunction "AVDD_8") (pintype "passive"))
    )
    (net (code "53") (name "unconnected-(U2-BT_ANT-Pad26)") (class "Default")
      (node (ref "U2") (pin "26") (pinfunction "BT_ANT_26") (pintype "passive"))
    )
    (net (code "54") (name "unconnected-(U2-CTS-Pad22)") (class "Default")
      (node (ref "U2") (pin "22") (pinfunction "CTS_22") (pintype "passive"))
    )
    (net (code "55") (name "unconnected-(U2-DCD-Pad21)") (class "Default")
      (node (ref "U2") (pin "21") (pinfunction "DCD_21") (pintype "passive"))
    )
    (net (code "56") (name "unconnected-(U2-DTR-Pad19)") (class "Default")
      (node (ref "U2") (pin "19") (pinfunction "DTR_19") (pintype "passive"))
    )
    (net (code "57") (name "unconnected-(U2-MICN-Pad4)") (class "Default")
      (node (ref "U2") (pin "4") (pinfunction "MICN_4") (pintype "passive"))
    )
    (net (code "58") (name "unconnected-(U2-MICP-Pad3)") (class "Default")
      (node (ref "U2") (pin "3") (pinfunction "MICP_3") (pintype "passive"))
    )
    (net (code "59") (name "unconnected-(U2-PCM_CLK-Pad30)") (class "Default")
      (node (ref "U2") (pin "30") (pinfunction "PCM_CLK_30") (pintype "passive"))
    )
    (net (code "60") (name "unconnected-(U2-PCM_IN-Pad32)") (class "Default")
      (node (ref "U2") (pin "32") (pinfunction "PCM_IN_32") (pintype "passive"))
    )
    (net (code "61") (name "unconnected-(U2-PCM_OUT-Pad33)") (class "Default")
      (node (ref "U2") (pin "33") (pinfunction "PCM_OUT_33") (pintype "passive"))
    )
    (net (code "62") (name "unconnected-(U2-PCM_SYNC-Pad31)") (class "Default")
      (node (ref "U2") (pin "31") (pinfunction "PCM_SYNC_31") (pintype "passive"))
    )
    (net (code "63") (name "unconnected-(U2-RESERVED-Pad15)") (class "Default")
      (node (ref "U2") (pin "15") (pinfunction "RESERVED_15") (pintype "passive"))
    )
    (net (code "64") (name "unconnected-(U2-RFTXMON-Pad25)") (class "Default")
      (node (ref "U2") (pin "25") (pinfunction "RFTXMON_25") (pintype "passive"))
    )
    (net (code "65") (name "unconnected-(U2-RI-Pad20)") (class "Default")
      (node (ref "U2") (pin "20") (pinfunction "RI_20") (pintype "passive"))
    )
    (net (code "66") (name "unconnected-(U2-RTS-Pad23)") (class "Default")
      (node (ref "U2") (pin "23") (pinfunction "RTS_23") (pintype "passive"))
    )
    (net (code "67") (name "unconnected-(U2-RXD_AUX-Pad28)") (class "Default")
      (node (ref "U2") (pin "28") (pinfunction "RXD_AUX_28") (pintype "passive"))
    )
    (net (code "68") (name "unconnected-(U2-SPK1N-Pad6)") (class "Default")
      (node (ref "U2") (pin "6") (pinfunction "SPK1N_6") (pintype "passive"))
    )
    (net (code "69") (name "unconnected-(U2-SPK1P-Pad5)") (class "Default")
      (node (ref "U2") (pin "5") (pinfunction "SPK1P_5") (pintype "passive"))
    )
    (net (code "70") (name "unconnected-(U2-SPK2P-Pad2)") (class "Default")
      (node (ref "U2") (pin "2") (pinfunction "SPK2P_2") (pintype "passive"))
    )
    (net (code "71") (name "unconnected-(U2-TXD_AUX-Pad29)") (class "Default")
      (node (ref "U2") (pin "29") (pinfunction "TXD_AUX_29") (pintype "passive"))
    )
    (net (code "72") (name "unconnected-(U2-VRTC-Pad44)") (class "Default")
      (node (ref "U2") (pin "44") (pinfunction "VRTC_44") (pintype "passive"))
    )
  )
)
